# ME433.net
KiCad netlist of a schematic drawn in EAGLE
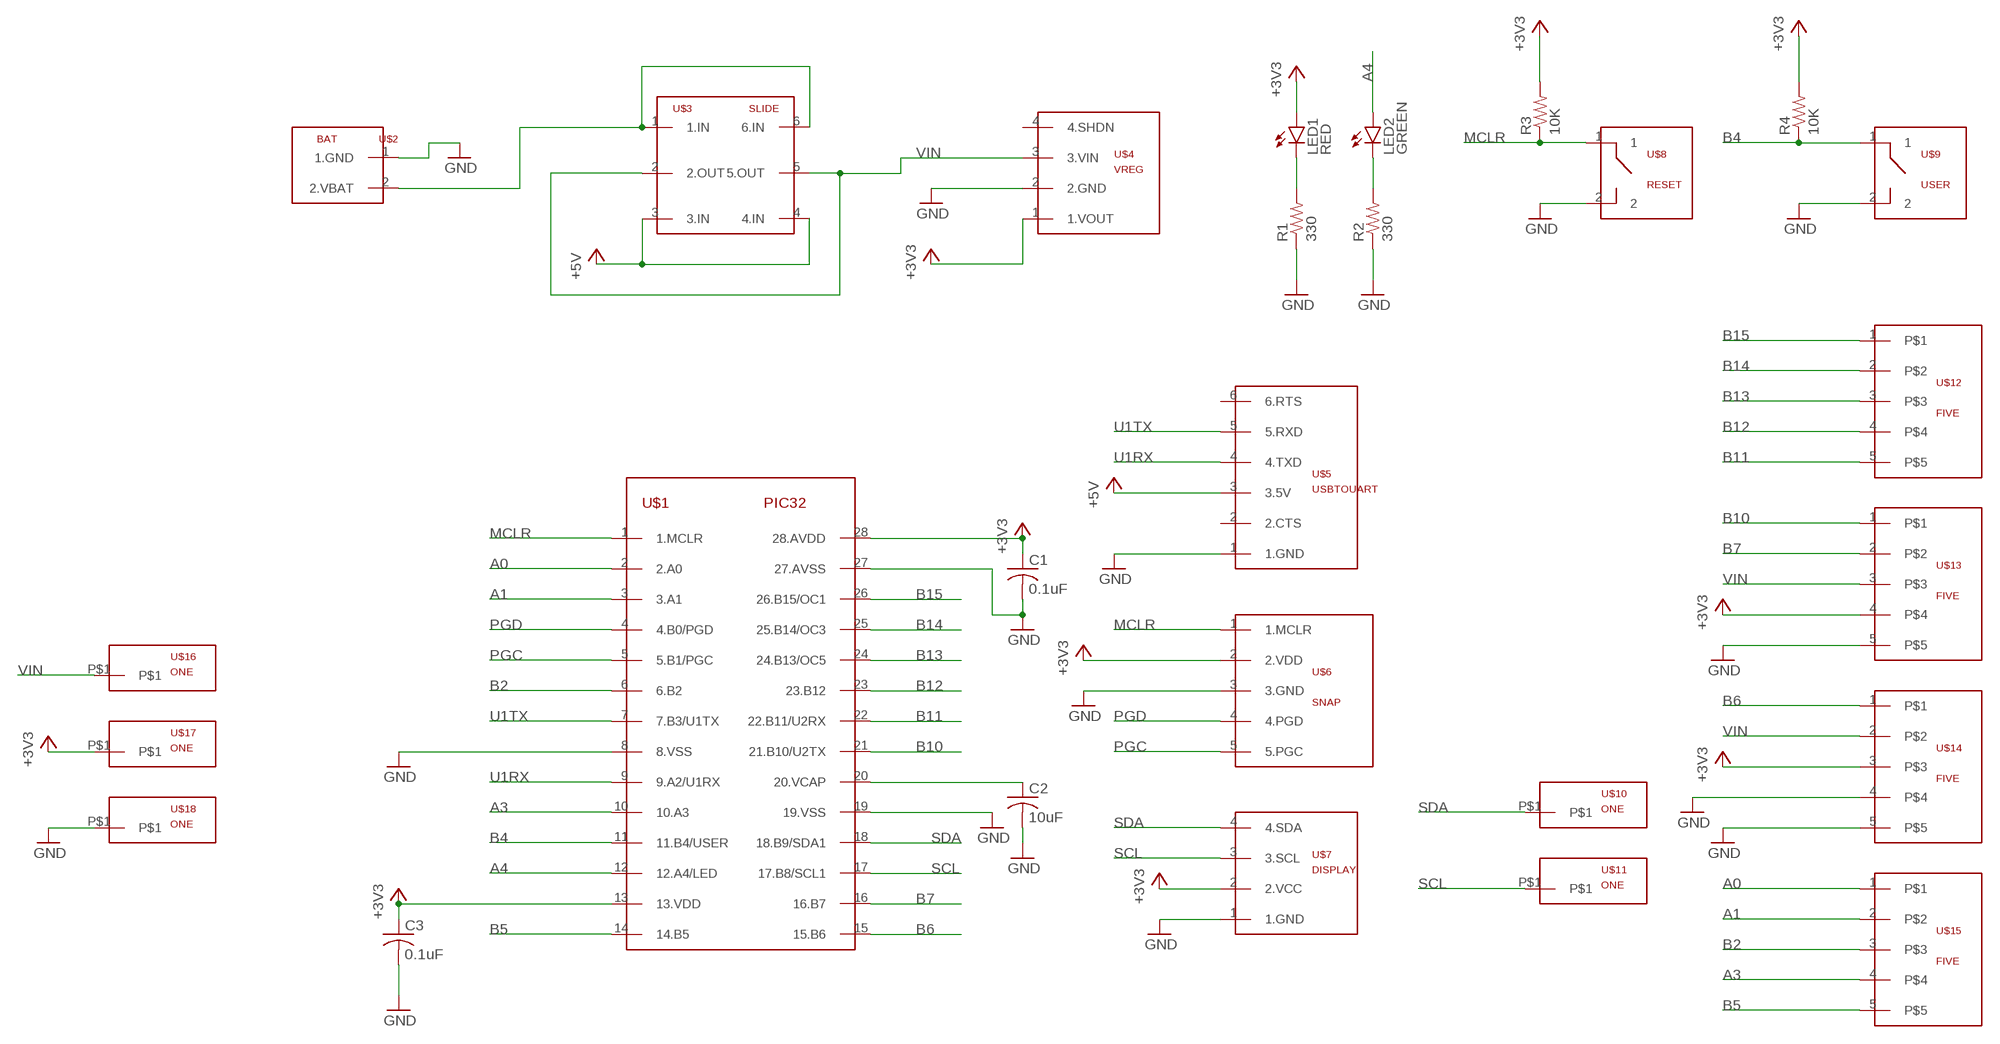
[diagram p0: schematic, sheet 1]

(export (version "E")
  (design (tool "Eeschema 10.0.6"))
  (components
    (comp (ref "C1")
      (value "0.1uF")
      (footprint "eagle-import:C025-024X044")
      (libsource (lib "eagle-import") (part "C-US025-024X044"))
    )
    (comp (ref "C2")
      (value "10uF")
      (footprint "eagle-import:C025-024X044")
      (libsource (lib "eagle-import") (part "C-US025-024X044"))
    )
    (comp (ref "C3")
      (value "0.1uF")
      (footprint "eagle-import:C025-024X044")
      (libsource (lib "eagle-import") (part "C-US025-024X044"))
    )
    (comp (ref "LED1")
      (value "RED")
      (footprint "eagle-import:LED3MM")
      (libsource (lib "eagle-import") (part "LED3MM"))
    )
    (comp (ref "LED2")
      (value "GREEN")
      (footprint "eagle-import:LED3MM")
      (libsource (lib "eagle-import") (part "LED3MM"))
    )
    (comp (ref "R1")
      (value "330")
      (footprint "eagle-import:0204_7")
      (libsource (lib "eagle-import") (part "R-US_0204/7"))
    )
    (comp (ref "R2")
      (value "330")
      (footprint "eagle-import:0204_7")
      (libsource (lib "eagle-import") (part "R-US_0204/7"))
    )
    (comp (ref "R3")
      (value "10K")
      (footprint "eagle-import:0204_7")
      (libsource (lib "eagle-import") (part "R-US_0204/7"))
    )
    (comp (ref "R4")
      (value "10K")
      (footprint "eagle-import:0204_7")
      (libsource (lib "eagle-import") (part "R-US_0204/7"))
    )
    (comp (ref "U$1")
      (value "PIC32")
      (footprint "eagle-import:DIL28-3")
      (libsource (lib "eagle-import") (part "PIC32"))
    )
    (comp (ref "U$2")
      (value "BAT")
      (footprint "eagle-import:BAT")
      (libsource (lib "eagle-import") (part "BAT"))
    )
    (comp (ref "U$3")
      (value "SLIDE")
      (footprint "eagle-import:SLIDE")
      (libsource (lib "eagle-import") (part "SLIDE"))
    )
    (comp (ref "U$4")
      (value "VREG")
      (footprint "eagle-import:VREG")
      (libsource (lib "eagle-import") (part "VREG"))
    )
    (comp (ref "U$5")
      (value "USBTOUART")
      (footprint "eagle-import:USBTOUART")
      (libsource (lib "eagle-import") (part "USBTOUART"))
    )
    (comp (ref "U$6")
      (value "SNAP")
      (footprint "eagle-import:SNAP")
      (libsource (lib "eagle-import") (part "SNAP"))
    )
    (comp (ref "U$7")
      (value "DISPLAY")
      (footprint "eagle-import:DISPLAY")
      (libsource (lib "eagle-import") (part "DISPLAY"))
    )
    (comp (ref "U$8")
      (value "RESET")
      (footprint "eagle-import:BUTTON")
      (libsource (lib "eagle-import") (part "BUTTON"))
    )
    (comp (ref "U$9")
      (value "USER")
      (footprint "eagle-import:BUTTON")
      (libsource (lib "eagle-import") (part "BUTTON"))
    )
    (comp (ref "U$10")
      (value "ONE")
      (footprint "eagle-import:ONE")
      (libsource (lib "eagle-import") (part "ONE"))
    )
    (comp (ref "U$11")
      (value "ONE")
      (footprint "eagle-import:ONE")
      (libsource (lib "eagle-import") (part "ONE"))
    )
    (comp (ref "U$12")
      (value "FIVE")
      (footprint "eagle-import:FIVE")
      (libsource (lib "eagle-import") (part "FIVE"))
    )
    (comp (ref "U$13")
      (value "FIVE")
      (footprint "eagle-import:FIVE")
      (libsource (lib "eagle-import") (part "FIVE"))
    )
    (comp (ref "U$14")
      (value "FIVE")
      (footprint "eagle-import:FIVE")
      (libsource (lib "eagle-import") (part "FIVE"))
    )
    (comp (ref "U$15")
      (value "FIVE")
      (footprint "eagle-import:FIVE")
      (libsource (lib "eagle-import") (part "FIVE"))
    )
    (comp (ref "U$16")
      (value "ONE")
      (footprint "eagle-import:ONE")
      (libsource (lib "eagle-import") (part "ONE"))
    )
    (comp (ref "U$17")
      (value "ONE")
      (footprint "eagle-import:ONE")
      (libsource (lib "eagle-import") (part "ONE"))
    )
    (comp (ref "U$18")
      (value "ONE")
      (footprint "eagle-import:ONE")
      (libsource (lib "eagle-import") (part "ONE"))
    )
  )
  (nets
    (net (code "1") (name "+3V3") (class "Default")
      (node (ref "C1") (pin "1") (pinfunction "1_1") (pintype "passive"))
      (node (ref "C3") (pin "1") (pinfunction "1_1") (pintype "passive"))
      (node (ref "LED1") (pin "A") (pinfunction "A_A") (pintype "passive"))
      (node (ref "R3") (pin "2") (pinfunction "2_2") (pintype "passive"))
      (node (ref "R4") (pin "2") (pinfunction "2_2") (pintype "passive"))
      (node (ref "U$1") (pin "13") (pinfunction "13.VDD_13") (pintype "bidirectional"))
      (node (ref "U$1") (pin "28") (pinfunction "28.AVDD_28") (pintype "bidirectional"))
      (node (ref "U$13") (pin "4") (pinfunction "P$4_4") (pintype "bidirectional"))
      (node (ref "U$14") (pin "3") (pinfunction "P$3_3") (pintype "bidirectional"))
      (node (ref "U$17") (pin "P$1") (pinfunction "P$1_P$1") (pintype "bidirectional"))
      (node (ref "U$4") (pin "1") (pinfunction "1.VOUT_1") (pintype "bidirectional"))
      (node (ref "U$6") (pin "2") (pinfunction "2.VDD_2") (pintype "bidirectional"))
      (node (ref "U$7") (pin "2") (pinfunction "2.VCC_2") (pintype "bidirectional"))
    )
    (net (code "2") (name "+5V") (class "Default")
      (node (ref "U$3") (pin "3") (pinfunction "3.IN_3") (pintype "bidirectional"))
      (node (ref "U$3") (pin "4") (pinfunction "4.IN_4") (pintype "bidirectional"))
      (node (ref "U$5") (pin "3") (pinfunction "3.5V_3") (pintype "bidirectional"))
    )
    (net (code "3") (name "/A0") (class "Default")
      (node (ref "U$1") (pin "2") (pinfunction "2.A0_2") (pintype "bidirectional"))
      (node (ref "U$15") (pin "1") (pinfunction "P$1_1") (pintype "bidirectional"))
    )
    (net (code "4") (name "/A1") (class "Default")
      (node (ref "U$1") (pin "3") (pinfunction "3.A1_3") (pintype "bidirectional"))
      (node (ref "U$15") (pin "2") (pinfunction "P$2_2") (pintype "bidirectional"))
    )
    (net (code "5") (name "/A3") (class "Default")
      (node (ref "U$1") (pin "10") (pinfunction "10.A3_10") (pintype "bidirectional"))
      (node (ref "U$15") (pin "4") (pinfunction "P$4_4") (pintype "bidirectional"))
    )
    (net (code "6") (name "/A4") (class "Default")
      (node (ref "LED2") (pin "A") (pinfunction "A_A") (pintype "passive"))
      (node (ref "U$1") (pin "12") (pinfunction "12.A4/LED_12") (pintype "bidirectional"))
    )
    (net (code "7") (name "/B2") (class "Default")
      (node (ref "U$1") (pin "6") (pinfunction "6.B2_6") (pintype "bidirectional"))
      (node (ref "U$15") (pin "3") (pinfunction "P$3_3") (pintype "bidirectional"))
    )
    (net (code "8") (name "/B4") (class "Default")
      (node (ref "R4") (pin "1") (pinfunction "1_1") (pintype "passive"))
      (node (ref "U$1") (pin "11") (pinfunction "11.B4/USER_11") (pintype "bidirectional"))
      (node (ref "U$9") (pin "1") (pinfunction "1_1") (pintype "bidirectional"))
    )
    (net (code "9") (name "/B5") (class "Default")
      (node (ref "U$1") (pin "14") (pinfunction "14.B5_14") (pintype "bidirectional"))
      (node (ref "U$15") (pin "5") (pinfunction "P$5_5") (pintype "bidirectional"))
    )
    (net (code "10") (name "/B6") (class "Default")
      (node (ref "U$1") (pin "15") (pinfunction "15.B6_15") (pintype "bidirectional"))
      (node (ref "U$14") (pin "1") (pinfunction "P$1_1") (pintype "bidirectional"))
    )
    (net (code "11") (name "/B7") (class "Default")
      (node (ref "U$1") (pin "16") (pinfunction "16.B7_16") (pintype "bidirectional"))
      (node (ref "U$13") (pin "2") (pinfunction "P$2_2") (pintype "bidirectional"))
    )
    (net (code "12") (name "/B10") (class "Default")
      (node (ref "U$1") (pin "21") (pinfunction "21.B10/U2TX_21") (pintype "bidirectional"))
      (node (ref "U$13") (pin "1") (pinfunction "P$1_1") (pintype "bidirectional"))
    )
    (net (code "13") (name "/B11") (class "Default")
      (node (ref "U$1") (pin "22") (pinfunction "22.B11/U2RX_22") (pintype "bidirectional"))
      (node (ref "U$12") (pin "5") (pinfunction "P$5_5") (pintype "bidirectional"))
    )
    (net (code "14") (name "/B12") (class "Default")
      (node (ref "U$1") (pin "23") (pinfunction "23.B12_23") (pintype "bidirectional"))
      (node (ref "U$12") (pin "4") (pinfunction "P$4_4") (pintype "bidirectional"))
    )
    (net (code "15") (name "/B13") (class "Default")
      (node (ref "U$1") (pin "24") (pinfunction "24.B13/OC5_24") (pintype "bidirectional"))
      (node (ref "U$12") (pin "3") (pinfunction "P$3_3") (pintype "bidirectional"))
    )
    (net (code "16") (name "/B14") (class "Default")
      (node (ref "U$1") (pin "25") (pinfunction "25.B14/OC3_25") (pintype "bidirectional"))
      (node (ref "U$12") (pin "2") (pinfunction "P$2_2") (pintype "bidirectional"))
    )
    (net (code "17") (name "/B15") (class "Default")
      (node (ref "U$1") (pin "26") (pinfunction "26.B15/OC1_26") (pintype "bidirectional"))
      (node (ref "U$12") (pin "1") (pinfunction "P$1_1") (pintype "bidirectional"))
    )
    (net (code "18") (name "/MCLR") (class "Default")
      (node (ref "R3") (pin "1") (pinfunction "1_1") (pintype "passive"))
      (node (ref "U$1") (pin "1") (pinfunction "1.MCLR_1") (pintype "bidirectional"))
      (node (ref "U$6") (pin "1") (pinfunction "1.MCLR_1") (pintype "bidirectional"))
      (node (ref "U$8") (pin "1") (pinfunction "1_1") (pintype "bidirectional"))
    )
    (net (code "19") (name "/PGC") (class "Default")
      (node (ref "U$1") (pin "5") (pinfunction "5.B1/PGC_5") (pintype "bidirectional"))
      (node (ref "U$6") (pin "5") (pinfunction "5.PGC_5") (pintype "bidirectional"))
    )
    (net (code "20") (name "/PGD") (class "Default")
      (node (ref "U$1") (pin "4") (pinfunction "4.B0/PGD_4") (pintype "bidirectional"))
      (node (ref "U$6") (pin "4") (pinfunction "4.PGD_4") (pintype "bidirectional"))
    )
    (net (code "21") (name "/SCL") (class "Default")
      (node (ref "U$1") (pin "17") (pinfunction "17.B8/SCL1_17") (pintype "bidirectional"))
      (node (ref "U$11") (pin "P$1") (pinfunction "P$1_P$1") (pintype "bidirectional"))
      (node (ref "U$7") (pin "3") (pinfunction "3.SCL_3") (pintype "bidirectional"))
    )
    (net (code "22") (name "/SDA") (class "Default")
      (node (ref "U$1") (pin "18") (pinfunction "18.B9/SDA1_18") (pintype "bidirectional"))
      (node (ref "U$10") (pin "P$1") (pinfunction "P$1_P$1") (pintype "bidirectional"))
      (node (ref "U$7") (pin "4") (pinfunction "4.SDA_4") (pintype "bidirectional"))
    )
    (net (code "23") (name "/U1RX") (class "Default")
      (node (ref "U$1") (pin "9") (pinfunction "9.A2/U1RX_9") (pintype "bidirectional"))
      (node (ref "U$5") (pin "4") (pinfunction "4.TXD_4") (pintype "bidirectional"))
    )
    (net (code "24") (name "/U1TX") (class "Default")
      (node (ref "U$1") (pin "7") (pinfunction "7.B3/U1TX_7") (pintype "bidirectional"))
      (node (ref "U$5") (pin "5") (pinfunction "5.RXD_5") (pintype "bidirectional"))
    )
    (net (code "25") (name "/VIN") (class "Default")
      (node (ref "U$13") (pin "3") (pinfunction "P$3_3") (pintype "bidirectional"))
      (node (ref "U$14") (pin "2") (pinfunction "P$2_2") (pintype "bidirectional"))
      (node (ref "U$16") (pin "P$1") (pinfunction "P$1_P$1") (pintype "bidirectional"))
      (node (ref "U$3") (pin "2") (pinfunction "2.OUT_2") (pintype "bidirectional"))
      (node (ref "U$3") (pin "5") (pinfunction "5.OUT_5") (pintype "bidirectional"))
      (node (ref "U$4") (pin "3") (pinfunction "3.VIN_3") (pintype "bidirectional"))
    )
    (net (code "26") (name "GND") (class "Default")
      (node (ref "C1") (pin "2") (pinfunction "2_2") (pintype "passive"))
      (node (ref "C2") (pin "2") (pinfunction "2_2") (pintype "passive"))
      (node (ref "C3") (pin "2") (pinfunction "2_2") (pintype "passive"))
      (node (ref "R1") (pin "1") (pinfunction "1_1") (pintype "passive"))
      (node (ref "R2") (pin "1") (pinfunction "1_1") (pintype "passive"))
      (node (ref "U$1") (pin "19") (pinfunction "19.VSS_19") (pintype "bidirectional"))
      (node (ref "U$1") (pin "27") (pinfunction "27.AVSS_27") (pintype "bidirectional"))
      (node (ref "U$1") (pin "8") (pinfunction "8.VSS_8") (pintype "bidirectional"))
      (node (ref "U$13") (pin "5") (pinfunction "P$5_5") (pintype "bidirectional"))
      (node (ref "U$14") (pin "4") (pinfunction "P$4_4") (pintype "bidirectional"))
      (node (ref "U$14") (pin "5") (pinfunction "P$5_5") (pintype "bidirectional"))
      (node (ref "U$18") (pin "P$1") (pinfunction "P$1_P$1") (pintype "bidirectional"))
      (node (ref "U$2") (pin "1") (pinfunction "1.GND_1") (pintype "bidirectional"))
      (node (ref "U$4") (pin "2") (pinfunction "2.GND_2") (pintype "bidirectional"))
      (node (ref "U$5") (pin "1") (pinfunction "1.GND_1") (pintype "bidirectional"))
      (node (ref "U$6") (pin "3") (pinfunction "3.GND_3") (pintype "bidirectional"))
      (node (ref "U$7") (pin "1") (pinfunction "1.GND_1") (pintype "bidirectional"))
      (node (ref "U$8") (pin "2") (pinfunction "2_2") (pintype "bidirectional"))
      (node (ref "U$9") (pin "2") (pinfunction "2_2") (pintype "bidirectional"))
    )
    (net (code "27") (name "Net-(LED1-C)") (class "Default")
      (node (ref "LED1") (pin "K") (pinfunction "C_K") (pintype "passive"))
      (node (ref "R1") (pin "2") (pinfunction "2_2") (pintype "passive"))
    )
    (net (code "28") (name "Net-(LED2-C)") (class "Default")
      (node (ref "LED2") (pin "K") (pinfunction "C_K") (pintype "passive"))
      (node (ref "R2") (pin "2") (pinfunction "2_2") (pintype "passive"))
    )
    (net (code "29") (name "Net-(U$1-20.VCAP)") (class "Default")
      (node (ref "C2") (pin "1") (pinfunction "1_1") (pintype "passive"))
      (node (ref "U$1") (pin "20") (pinfunction "20.VCAP_20") (pintype "bidirectional"))
    )
    (net (code "30") (name "Net-(U$2-2.VBAT)") (class "Default")
      (node (ref "U$2") (pin "2") (pinfunction "2.VBAT_2") (pintype "bidirectional"))
      (node (ref "U$3") (pin "1") (pinfunction "1.IN_1") (pintype "bidirectional"))
      (node (ref "U$3") (pin "6") (pinfunction "6.IN_6") (pintype "bidirectional"))
    )
    (net (code "31") (name "unconnected-(U$4-4.SHDN-Pad4)") (class "Default")
      (node (ref "U$4") (pin "4") (pinfunction "4.SHDN_4") (pintype "bidirectional"))
    )
    (net (code "32") (name "unconnected-(U$5-2.CTS-Pad2)") (class "Default")
      (node (ref "U$5") (pin "2") (pinfunction "2.CTS_2") (pintype "bidirectional"))
    )
    (net (code "33") (name "unconnected-(U$5-6.RTS-Pad6)") (class "Default")
      (node (ref "U$5") (pin "6") (pinfunction "6.RTS_6") (pintype "bidirectional"))
    )
  )
)
